# SolarPanel7Cells.net
KiCad netlist of a schematic drawn in Altium Designer
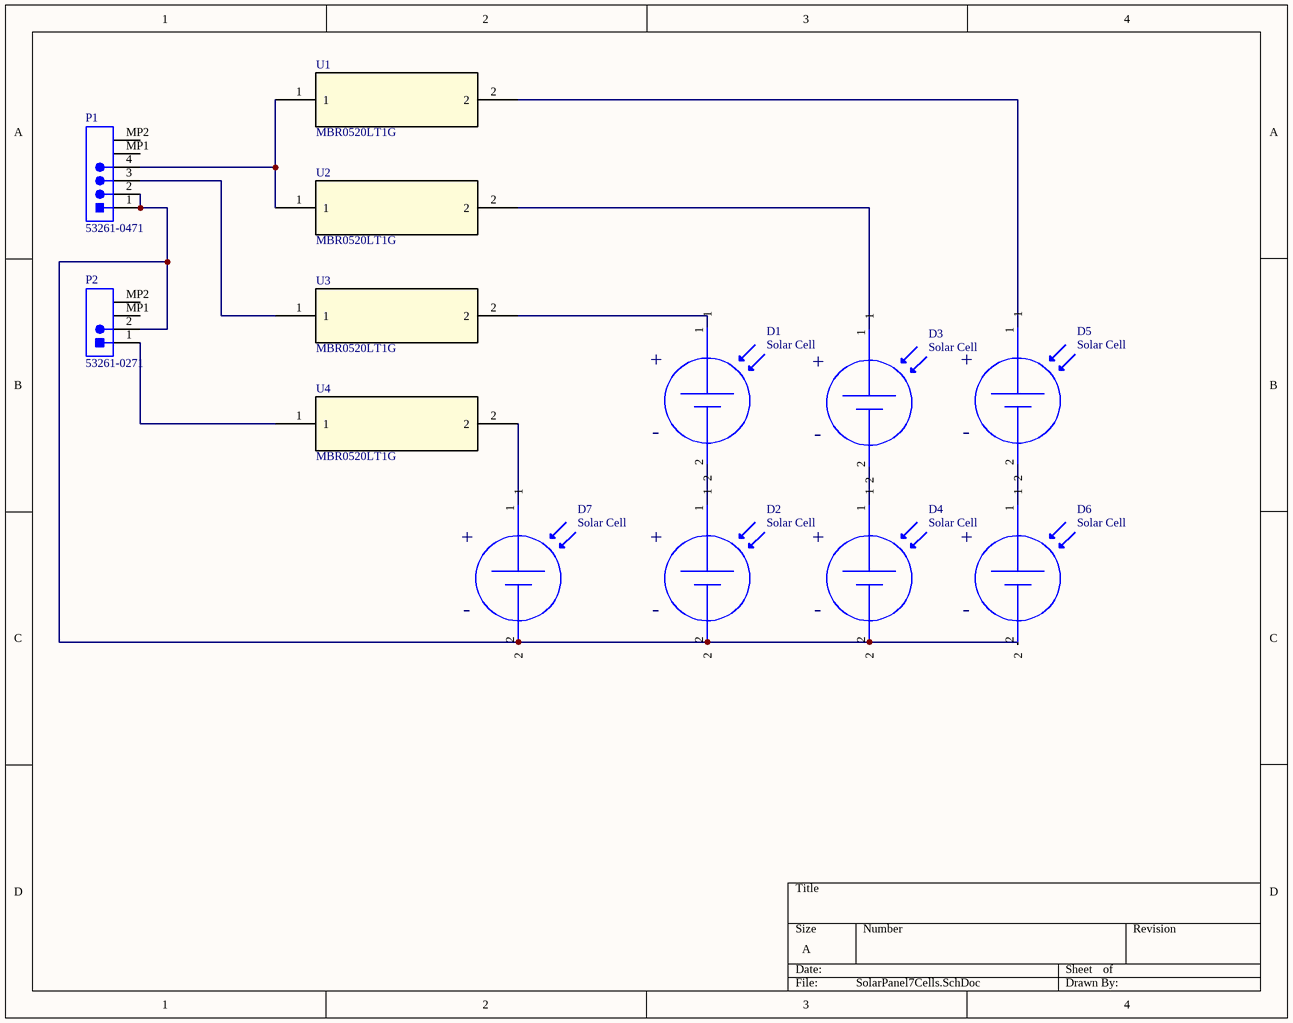
[diagram p0: SolarPanel7Cells.SchDoc]

(export (version "E")
  (design (tool "Eeschema 10.0.6"))
  (components
    (comp (ref "D1")
      (value "Solar Cell")
      (description "SolAero BJT Space Solar Cell")
      (libsource (lib "SolarPanel7Cells") (part "SolAeroBJTSpaceSolarCell"))
    )
    (comp (ref "D2")
      (value "Solar Cell")
      (description "SolAero BJT Space Solar Cell")
      (libsource (lib "SolarPanel7Cells") (part "SolAeroBJTSpaceSolarCell"))
    )
    (comp (ref "D3")
      (value "Solar Cell")
      (description "SolAero BJT Space Solar Cell")
      (libsource (lib "SolarPanel7Cells") (part "SolAeroBJTSpaceSolarCell"))
    )
    (comp (ref "D4")
      (value "Solar Cell")
      (description "SolAero BJT Space Solar Cell")
      (libsource (lib "SolarPanel7Cells") (part "SolAeroBJTSpaceSolarCell"))
    )
    (comp (ref "D5")
      (value "Solar Cell")
      (description "SolAero BJT Space Solar Cell")
      (libsource (lib "SolarPanel7Cells") (part "SolAeroBJTSpaceSolarCell"))
    )
    (comp (ref "D6")
      (value "Solar Cell")
      (description "SolAero BJT Space Solar Cell")
      (libsource (lib "SolarPanel7Cells") (part "SolAeroBJTSpaceSolarCell"))
    )
    (comp (ref "D7")
      (value "Solar Cell")
      (description "SolAero BJT Space Solar Cell")
      (libsource (lib "SolarPanel7Cells") (part "SolAeroBJTSpaceSolarCell"))
    )
    (comp (ref "P1")
      (value "53261-0471")
      (footprint "MOLEX-53261-0471_V")
      (description "Male Header, Pitch 1.25 mm, 1 x 4 Position, Height 3.4 mm, -40 to 85 degC, RoHS, Tape and Reel")
      (fields (field (name "MANUFACTURER") "Molex"))
      (libsource (lib "SolarPanel7Cells") (part "CMP-2000-05238-1"))
    )
    (comp (ref "P2")
      (value "53261-0271")
      (footprint "MOLX-53261-0271_V")
      (description "PicoBlade(TM) Header, Right Angle, -40 to 85 degC, 2-Pin SMD, RoHS, Tape and Reel")
      (fields (field (name "MANUFACTURER") "Molex"))
      (libsource (lib "SolarPanel7Cells") (part "CMP-2000-05633-1"))
    )
    (comp (ref "U1")
      (value "MBR0520LT1G")
      (footprint "SOD-123")
      (description "Imported")
      (fields (field (name "COPYRIGHT") "Copyright (C) 2015 Accelerated Designs. All rights reserved"))
      (libsource (lib "SolarPanel7Cells") (part "MBR0520LT1G"))
    )
    (comp (ref "U2")
      (value "MBR0520LT1G")
      (footprint "SOD-123")
      (description "Imported")
      (fields (field (name "COPYRIGHT") "Copyright (C) 2015 Accelerated Designs. All rights reserved"))
      (libsource (lib "SolarPanel7Cells") (part "MBR0520LT1G"))
    )
    (comp (ref "U3")
      (value "MBR0520LT1G")
      (footprint "SOD-123")
      (description "Imported")
      (fields (field (name "COPYRIGHT") "Copyright (C) 2015 Accelerated Designs. All rights reserved"))
      (libsource (lib "SolarPanel7Cells") (part "MBR0520LT1G"))
    )
    (comp (ref "U4")
      (value "MBR0520LT1G")
      (footprint "SOD-123")
      (description "Imported")
      (fields (field (name "COPYRIGHT") "Copyright (C) 2015 Accelerated Designs. All rights reserved"))
      (libsource (lib "SolarPanel7Cells") (part "MBR0520LT1G"))
    )
  )
  (nets
    (net (code "1") (name "Net-(D1-Pad1)") (class "Default")
      (node (ref "D1") (pin "1") (pinfunction "1_1") (pintype "power_in"))
      (node (ref "U3") (pin "2") (pinfunction "2_2") (pintype "passive"))
    )
    (net (code "2") (name "Net-(D1-Pad2)") (class "Default")
      (node (ref "D1") (pin "2") (pinfunction "2_2") (pintype "passive"))
      (node (ref "D2") (pin "1") (pinfunction "1_1") (pintype "power_in"))
    )
    (net (code "3") (name "Net-(D2-Pad2)") (class "Default")
      (node (ref "D2") (pin "2") (pinfunction "2_2") (pintype "passive"))
      (node (ref "D4") (pin "2") (pinfunction "2_2") (pintype "passive"))
      (node (ref "D6") (pin "2") (pinfunction "2_2") (pintype "passive"))
      (node (ref "D7") (pin "2") (pinfunction "2_2") (pintype "passive"))
      (node (ref "P1") (pin "1") (pinfunction "1_1") (pintype "passive"))
      (node (ref "P1") (pin "2") (pinfunction "2_2") (pintype "passive"))
      (node (ref "P2") (pin "2") (pinfunction "2_2") (pintype "passive"))
    )
    (net (code "4") (name "Net-(D3-Pad1)") (class "Default")
      (node (ref "D3") (pin "1") (pinfunction "1_1") (pintype "power_in"))
      (node (ref "U2") (pin "2") (pinfunction "2_2") (pintype "passive"))
    )
    (net (code "5") (name "Net-(D3-Pad2)") (class "Default")
      (node (ref "D3") (pin "2") (pinfunction "2_2") (pintype "passive"))
      (node (ref "D4") (pin "1") (pinfunction "1_1") (pintype "power_in"))
    )
    (net (code "6") (name "Net-(D5-Pad1)") (class "Default")
      (node (ref "D5") (pin "1") (pinfunction "1_1") (pintype "power_in"))
      (node (ref "U1") (pin "2") (pinfunction "2_2") (pintype "passive"))
    )
    (net (code "7") (name "Net-(D5-Pad2)") (class "Default")
      (node (ref "D5") (pin "2") (pinfunction "2_2") (pintype "passive"))
      (node (ref "D6") (pin "1") (pinfunction "1_1") (pintype "power_in"))
    )
    (net (code "8") (name "Net-(D7-Pad1)") (class "Default")
      (node (ref "D7") (pin "1") (pinfunction "1_1") (pintype "power_in"))
      (node (ref "U4") (pin "2") (pinfunction "2_2") (pintype "passive"))
    )
    (net (code "9") (name "Net-(P1-Pad3)") (class "Default")
      (node (ref "P1") (pin "3") (pinfunction "3_3") (pintype "passive"))
      (node (ref "U3") (pin "1") (pinfunction "1_1") (pintype "passive"))
    )
    (net (code "10") (name "Net-(P1-Pad4)") (class "Default")
      (node (ref "P1") (pin "4") (pinfunction "4_4") (pintype "passive"))
      (node (ref "U1") (pin "1") (pinfunction "1_1") (pintype "passive"))
      (node (ref "U2") (pin "1") (pinfunction "1_1") (pintype "passive"))
    )
    (net (code "11") (name "Net-(P2-Pad1)") (class "Default")
      (node (ref "P2") (pin "1") (pinfunction "1_1") (pintype "passive"))
      (node (ref "U4") (pin "1") (pinfunction "1_1") (pintype "passive"))
    )
    (net (code "12") (name "unconnected-(P1-PadMP1)") (class "Default")
      (node (ref "P1") (pin "MP1") (pinfunction "MP1_MP1") (pintype "passive"))
    )
    (net (code "13") (name "unconnected-(P1-PadMP2)") (class "Default")
      (node (ref "P1") (pin "MP2") (pinfunction "MP2_MP2") (pintype "passive"))
    )
    (net (code "14") (name "unconnected-(P2-PadMP1)") (class "Default")
      (node (ref "P2") (pin "MP1") (pinfunction "MP1_MP1") (pintype "passive"))
    )
    (net (code "15") (name "unconnected-(P2-PadMP2)") (class "Default")
      (node (ref "P2") (pin "MP2") (pinfunction "MP2_MP2") (pintype "passive"))
    )
  )
)
